# power_stage.net
KiCad netlist of a schematic drawn in Altium Designer
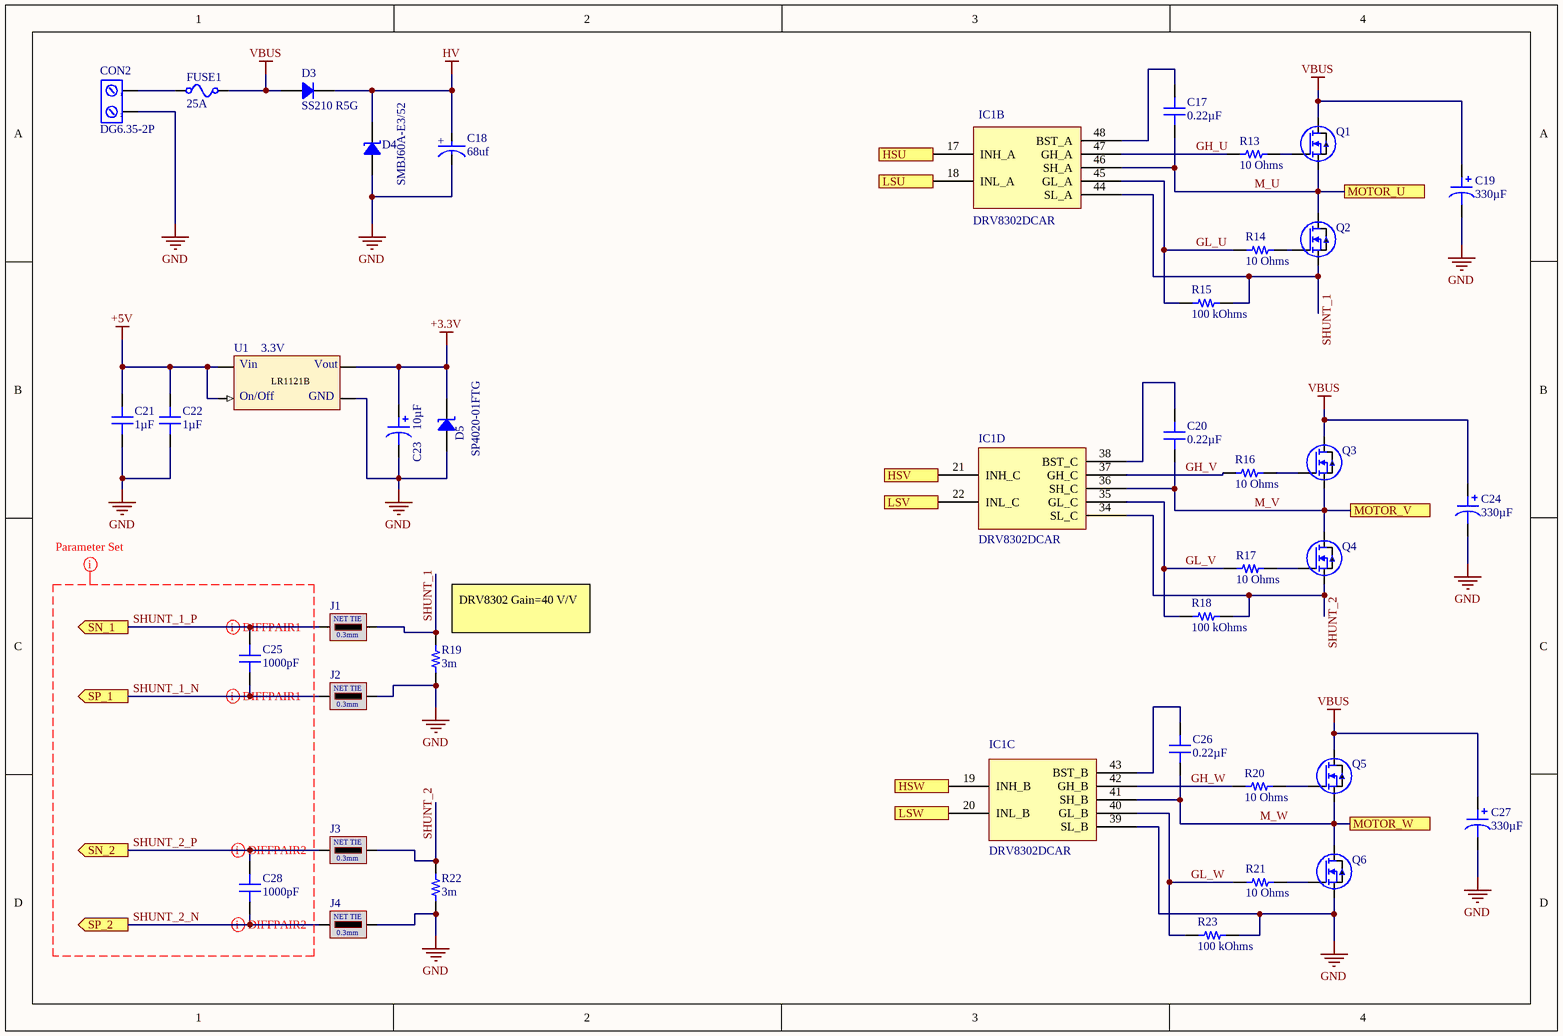
[diagram p0: power stage.SchDoc]

(export (version "E")
  (design (tool "Eeschema 10.0.6"))
  (components
    (comp (ref "C17")
      (value "0.22µF")
      (footprint "CAP 0603_1608")
      (description "CAP CER 0603 220NF 16V X7R 10%")
      (fields (field (name "PART NUMBER") "C0603C224K4RECAUTO") (field (name "MANUFACTURER") "KEMET"))
      (libsource (lib "Celestial Altium Library - altium_library") (part "Capacitor"))
    )
    (comp (ref "C18")
      (value "68uf")
      (footprint "10x10 radial smd cap")
      (description "68uf 100V 85C")
      (libsource (lib "My_Library_SMD_Electrlytic_Capacitor") (part "SC1J686M10010VR"))
    )
    (comp (ref "C19")
      (value "330µF")
      (footprint "CAP TH ALUM ELEC D10.00mm S5.00mm H26.50mm")
      (description "63V 331UF 20% HIGH RELIA-LEADED")
      (fields (field (name "PART NUMBER") "UHW1J331MPD") (field (name "MANUFACTURER") "Nichicon"))
      (libsource (lib "Celestial Altium Library - altium_library") (part "Polarised Capacitor"))
    )
    (comp (ref "C20")
      (value "0.22µF")
      (footprint "CAP 0603_1608")
      (description "CAP CER 0603 220NF 16V X7R 10%")
      (fields (field (name "PART NUMBER") "C0603C224K4RECAUTO") (field (name "MANUFACTURER") "KEMET"))
      (libsource (lib "Celestial Altium Library - altium_library") (part "Capacitor"))
    )
    (comp (ref "C21")
      (value "1µF")
      (footprint "CAP 0402_1005")
      (description "CAP CER 1UF 10V X7S 0402")
      (fields
        (field (name "PART NUMBER") "GRM155C71A105KE11D")
        (field (name "MANUFACTURER") "Murata Electronics")
      )
      (libsource (lib "Celestial Altium Library - altium_library") (part "Capacitor"))
    )
    (comp (ref "C22")
      (value "1µF")
      (footprint "CAP 0402_1005")
      (description "CAP CER 1UF 10V X7S 0402")
      (fields
        (field (name "PART NUMBER") "GRM155C71A105KE11D")
        (field (name "MANUFACTURER") "Murata Electronics")
      )
      (libsource (lib "Celestial Altium Library - altium_library") (part "Capacitor"))
    )
    (comp (ref "C23")
      (value "10µF")
      (footprint "CAP POL 1206_3216")
      (description "CAP TANT 10UF 10% 10V 1206")
      (fields (field (name "PART NUMBER") "T491S106K010AT") (field (name "MANUFACTURER") "KEMET"))
      (libsource (lib "Celestial Altium Library - altium_library") (part "Polarised Capacitor"))
    )
    (comp (ref "C24")
      (value "330µF")
      (footprint "CAP TH ALUM ELEC D10.00mm S5.00mm H26.50mm")
      (description "63V 331UF 20% HIGH RELIA-LEADED")
      (fields (field (name "PART NUMBER") "UHW1J331MPD") (field (name "MANUFACTURER") "Nichicon"))
      (libsource (lib "Celestial Altium Library - altium_library") (part "Polarised Capacitor"))
    )
    (comp (ref "C25")
      (value "1000pF")
      (footprint "CAP 0805_2012")
      (description "CAP CER 1000PF 100V X7R 0805")
      (fields (field (name "PART NUMBER") "CC0805JRX7R0BB102") (field (name "MANUFACTURER") "Yageo"))
      (libsource (lib "Celestial Altium Library - altium_library") (part "Capacitor"))
    )
    (comp (ref "C26")
      (value "0.22µF")
      (footprint "CAP 0603_1608")
      (description "CAP CER 0603 220NF 16V X7R 10%")
      (fields (field (name "PART NUMBER") "C0603C224K4RECAUTO") (field (name "MANUFACTURER") "KEMET"))
      (libsource (lib "Celestial Altium Library - altium_library") (part "Capacitor"))
    )
    (comp (ref "C27")
      (value "330µF")
      (footprint "CAP TH ALUM ELEC D10.00mm S5.00mm H26.50mm")
      (description "63V 331UF 20% HIGH RELIA-LEADED")
      (fields (field (name "PART NUMBER") "UHW1J331MPD") (field (name "MANUFACTURER") "Nichicon"))
      (libsource (lib "Celestial Altium Library - altium_library") (part "Polarised Capacitor"))
    )
    (comp (ref "C28")
      (value "1000pF")
      (footprint "CAP 0805_2012")
      (description "CAP CER 1000PF 100V X7R 0805")
      (fields (field (name "PART NUMBER") "CC0805JRX7R0BB102") (field (name "MANUFACTURER") "Yageo"))
      (libsource (lib "Celestial Altium Library - altium_library") (part "Capacitor"))
    )
    (comp (ref "CON2")
      (value "DG6.35-2P")
      (footprint "DG636-6.35-2P")
      (libsource (lib "My_Library_PCB_Terminal") (part "DG6.35-2P"))
    )
    (comp (ref "D3")
      (value "SS210 R5G")
      (footprint "DO214AA SMB")
      (description "DIODE SCHOTTKY 100V 2A DO214AA")
      (fields (field (name "MANUFACTURER") "Taiwan Semiconductor Corporation"))
      (libsource (lib "Celestial Altium Library - altium_library") (part "Diode"))
    )
    (comp (ref "D4")
      (value "SMBJ60A-E3/52")
      (footprint "DO214AA SMB")
      (description "TVS DIODE 60V 96.8V DO214AA")
      (fields (field (name "MANUFACTURER") "Vishay Semiconductor Diodes Division"))
      (libsource (lib "Celestial Altium Library - altium_library") (part "DIODE TVS UNI"))
    )
    (comp (ref "D5")
      (value "SP4020-01FTG")
      (footprint "SOD323")
      (description "TVS DIODE 3.3V 21.8V SOD323")
      (fields (field (name "MANUFACTURER") "Littelfuse Inc."))
      (libsource (lib "Celestial Altium Library - altium_library") (part "DIODE TVS UNI"))
    )
    (comp (ref "FUSE1")
      (value "25A")
      (footprint "3522 ATOF FUSE")
      (description "3522 ATOF automotive fuse")
      (libsource (lib "My_Library_ATOF_Fuse") (part "ATOF Fuse 3522"))
    )
    (comp (ref "IC1")
      (value "DRV8302DCAR")
      (footprint "TI HTSSOP-56 DCA")
      (description "IC MOTOR DRIVER 8V-60V 56HTSSOP")
      (fields (field (name "MANUFACTURER") "Texas Instruments"))
      (libsource (lib "Celestial Altium Library - altium_library") (part "TI DRV8302"))
    )
    (comp (ref "J1")
      (value "NET TIE 1")
      (footprint "net_tie_03mm")
      (libsource (lib "My_Library_Net_tie") (part "NET TIE 1"))
    )
    (comp (ref "J2")
      (value "NET TIE 1")
      (footprint "net_tie_03mm")
      (libsource (lib "My_Library_Net_tie") (part "NET TIE 1"))
    )
    (comp (ref "J3")
      (value "NET TIE 1")
      (footprint "net_tie_03mm")
      (libsource (lib "My_Library_Net_tie") (part "NET TIE 1"))
    )
    (comp (ref "J4")
      (value "NET TIE 1")
      (footprint "net_tie_03mm")
      (libsource (lib "My_Library_Net_tie") (part "NET TIE 1"))
    )
    (comp (ref "Q1")
      (value "STB100N10F7")
      (footprint "D2PAK")
      (libsource (lib "My_library_Mosfet") (part "STB100N10F7"))
    )
    (comp (ref "Q2")
      (value "STB100N10F7")
      (footprint "D2PAK")
      (libsource (lib "My_library_Mosfet") (part "STB100N10F7"))
    )
    (comp (ref "Q3")
      (value "STB100N10F7")
      (footprint "D2PAK")
      (libsource (lib "My_library_Mosfet") (part "STB100N10F7"))
    )
    (comp (ref "Q4")
      (value "STB100N10F7")
      (footprint "D2PAK")
      (libsource (lib "My_library_Mosfet") (part "STB100N10F7"))
    )
    (comp (ref "Q5")
      (value "STB100N10F7")
      (footprint "D2PAK")
      (libsource (lib "My_library_Mosfet") (part "STB100N10F7"))
    )
    (comp (ref "Q6")
      (value "STB100N10F7")
      (footprint "D2PAK")
      (libsource (lib "My_library_Mosfet") (part "STB100N10F7"))
    )
    (comp (ref "R13")
      (value "10 Ohms")
      (footprint "RES 1206_3216")
      (description "CRGCQ 1206 10R 1%")
      (fields
        (field (name "PART NUMBER") "CRGCQ1206F10R")
        (field (name "MANUFACTURER") "TE Connectivity Passive Product")
      )
      (libsource (lib "Celestial Altium Library - altium_library") (part "Resistor"))
    )
    (comp (ref "R14")
      (value "10 Ohms")
      (footprint "RES 1206_3216")
      (description "CRGCQ 1206 10R 1%")
      (fields
        (field (name "PART NUMBER") "CRGCQ1206F10R")
        (field (name "MANUFACTURER") "TE Connectivity Passive Product")
      )
      (libsource (lib "Celestial Altium Library - altium_library") (part "Resistor"))
    )
    (comp (ref "R15")
      (value "100 kOhms")
      (footprint "RES 1206_3216")
      (description "RES SMD 100K OHM 1% 1/4W 1206")
      (fields
        (field (name "PART NUMBER") "CRG1206F100K")
        (field (name "MANUFACTURER") "TE Connectivity Passive Product")
      )
      (libsource (lib "Celestial Altium Library - altium_library") (part "Resistor"))
    )
    (comp (ref "R16")
      (value "10 Ohms")
      (footprint "RES 1206_3216")
      (description "CRGCQ 1206 10R 1%")
      (fields
        (field (name "PART NUMBER") "CRGCQ1206F10R")
        (field (name "MANUFACTURER") "TE Connectivity Passive Product")
      )
      (libsource (lib "Celestial Altium Library - altium_library") (part "Resistor"))
    )
    (comp (ref "R17")
      (value "10 Ohms")
      (footprint "RES 1206_3216")
      (description "CRGCQ 1206 10R 1%")
      (fields
        (field (name "PART NUMBER") "CRGCQ1206F10R")
        (field (name "MANUFACTURER") "TE Connectivity Passive Product")
      )
      (libsource (lib "Celestial Altium Library - altium_library") (part "Resistor"))
    )
    (comp (ref "R18")
      (value "100 kOhms")
      (footprint "RES 1206_3216")
      (description "RES SMD 100K OHM 1% 1/4W 1206")
      (fields
        (field (name "PART NUMBER") "CRG1206F100K")
        (field (name "MANUFACTURER") "TE Connectivity Passive Product")
      )
      (libsource (lib "Celestial Altium Library - altium_library") (part "Resistor"))
    )
    (comp (ref "R19")
      (value "3m")
      (footprint "2512_bvt")
      (description "SMT Resistor")
      (libsource (lib "My_Library_Shunt_Resistor") (part "BVT2512"))
    )
    (comp (ref "R20")
      (value "10 Ohms")
      (footprint "RES 1206_3216")
      (description "CRGCQ 1206 10R 1%")
      (fields
        (field (name "PART NUMBER") "CRGCQ1206F10R")
        (field (name "MANUFACTURER") "TE Connectivity Passive Product")
      )
      (libsource (lib "Celestial Altium Library - altium_library") (part "Resistor"))
    )
    (comp (ref "R21")
      (value "10 Ohms")
      (footprint "RES 1206_3216")
      (description "CRGCQ 1206 10R 1%")
      (fields
        (field (name "PART NUMBER") "CRGCQ1206F10R")
        (field (name "MANUFACTURER") "TE Connectivity Passive Product")
      )
      (libsource (lib "Celestial Altium Library - altium_library") (part "Resistor"))
    )
    (comp (ref "R22")
      (value "3m")
      (footprint "2512_bvt")
      (description "SMT Resistor")
      (libsource (lib "My_Library_Shunt_Resistor") (part "BVT2512"))
    )
    (comp (ref "R23")
      (value "100 kOhms")
      (footprint "RES 1206_3216")
      (description "RES SMD 100K OHM 1% 1/4W 1206")
      (fields
        (field (name "PART NUMBER") "CRG1206F100K")
        (field (name "MANUFACTURER") "TE Connectivity Passive Product")
      )
      (libsource (lib "Celestial Altium Library - altium_library") (part "Resistor"))
    )
    (comp (ref "U1")
      (value "3.3V")
      (footprint "SOT25_LR2111")
      (description "200mA 7V LDO")
      (libsource (lib "My_Library_Linear_Regulator") (part "LR1121B_3V3"))
    )
  )
  (nets
    (net (code "1") (name "+3.3V") (class "Default")
      (node (ref "C23") (pin "1") (pinfunction "1_1") (pintype "passive"))
      (node (ref "D5") (pin "2") (pinfunction "2_2") (pintype "passive"))
      (node (ref "U1") (pin "1") (pinfunction "Vout_1") (pintype "power_in"))
    )
    (net (code "2") (name "+5V") (class "Default")
      (node (ref "C21") (pin "2") (pinfunction "2_2") (pintype "passive"))
      (node (ref "C22") (pin "2") (pinfunction "2_2") (pintype "passive"))
      (node (ref "U1") (pin "3") (pinfunction "Vin_3") (pintype "power_in"))
      (node (ref "U1") (pin "4") (pinfunction "ON/OFF_4") (pintype "input"))
    )
    (net (code "3") (name "/GH_U") (class "Default")
      (node (ref "IC1") (pin "47") (pinfunction "GH_A_47") (pintype "passive"))
      (node (ref "R13") (pin "1") (pinfunction "1_1") (pintype "passive"))
    )
    (net (code "4") (name "/GH_V") (class "Default")
      (node (ref "IC1") (pin "37") (pinfunction "GH_C_37") (pintype "passive"))
      (node (ref "R16") (pin "1") (pinfunction "1_1") (pintype "passive"))
    )
    (net (code "5") (name "/GH_W") (class "Default")
      (node (ref "IC1") (pin "42") (pinfunction "GH_B_42") (pintype "passive"))
      (node (ref "R20") (pin "1") (pinfunction "1_1") (pintype "passive"))
    )
    (net (code "6") (name "/GL_U") (class "Default")
      (node (ref "IC1") (pin "45") (pinfunction "GL_A_45") (pintype "passive"))
      (node (ref "R14") (pin "1") (pinfunction "1_1") (pintype "passive"))
      (node (ref "R15") (pin "1") (pinfunction "1_1") (pintype "passive"))
    )
    (net (code "7") (name "/GL_V") (class "Default")
      (node (ref "IC1") (pin "35") (pinfunction "GL_C_35") (pintype "passive"))
      (node (ref "R17") (pin "1") (pinfunction "1_1") (pintype "passive"))
      (node (ref "R18") (pin "1") (pinfunction "1_1") (pintype "passive"))
    )
    (net (code "8") (name "/GL_W") (class "Default")
      (node (ref "IC1") (pin "40") (pinfunction "GL_B_40") (pintype "passive"))
      (node (ref "R21") (pin "1") (pinfunction "1_1") (pintype "passive"))
      (node (ref "R23") (pin "1") (pinfunction "1_1") (pintype "passive"))
    )
    (net (code "9") (name "/HSU") (class "Default")
      (node (ref "IC1") (pin "17") (pinfunction "INH_A_17") (pintype "passive"))
    )
    (net (code "10") (name "/HSV") (class "Default")
      (node (ref "IC1") (pin "21") (pinfunction "INH_C_21") (pintype "passive"))
    )
    (net (code "11") (name "/HSW") (class "Default")
      (node (ref "IC1") (pin "19") (pinfunction "INH_B_19") (pintype "passive"))
    )
    (net (code "12") (name "/LSU") (class "Default")
      (node (ref "IC1") (pin "18") (pinfunction "INL_A_18") (pintype "passive"))
    )
    (net (code "13") (name "/LSV") (class "Default")
      (node (ref "IC1") (pin "22") (pinfunction "INL_C_22") (pintype "passive"))
    )
    (net (code "14") (name "/LSW") (class "Default")
      (node (ref "IC1") (pin "20") (pinfunction "INL_B_20") (pintype "passive"))
    )
    (net (code "15") (name "/M_U") (class "Default")
      (node (ref "C17") (pin "1") (pinfunction "1_1") (pintype "passive"))
      (node (ref "IC1") (pin "46") (pinfunction "SH_A_46") (pintype "passive"))
      (node (ref "Q1") (pin "3") (pinfunction "S_3") (pintype "passive"))
      (node (ref "Q2") (pin "2") (pinfunction "D_2") (pintype "passive"))
    )
    (net (code "16") (name "/M_V") (class "Default")
      (node (ref "C20") (pin "1") (pinfunction "1_1") (pintype "passive"))
      (node (ref "IC1") (pin "36") (pinfunction "SH_C_36") (pintype "passive"))
      (node (ref "Q3") (pin "3") (pinfunction "S_3") (pintype "passive"))
      (node (ref "Q4") (pin "2") (pinfunction "D_2") (pintype "passive"))
    )
    (net (code "17") (name "/M_W") (class "Default")
      (node (ref "C26") (pin "1") (pinfunction "1_1") (pintype "passive"))
      (node (ref "IC1") (pin "41") (pinfunction "SH_B_41") (pintype "passive"))
      (node (ref "Q5") (pin "3") (pinfunction "S_3") (pintype "passive"))
      (node (ref "Q6") (pin "2") (pinfunction "D_2") (pintype "passive"))
    )
    (net (code "18") (name "/SHUNT_1") (class "Default")
      (node (ref "IC1") (pin "44") (pinfunction "SL_A_44") (pintype "passive"))
      (node (ref "J1") (pin "2") (pinfunction "2_2") (pintype "passive"))
      (node (ref "Q2") (pin "3") (pinfunction "S_3") (pintype "passive"))
      (node (ref "R15") (pin "2") (pinfunction "2_2") (pintype "passive"))
      (node (ref "R19") (pin "2") (pinfunction "2_2") (pintype "passive"))
    )
    (net (code "19") (name "/SHUNT_1_N") (class "Default")
      (node (ref "C25") (pin "1") (pinfunction "1_1") (pintype "passive"))
      (node (ref "J2") (pin "1") (pinfunction "1_1") (pintype "passive"))
    )
    (net (code "20") (name "/SHUNT_1_P") (class "Default")
      (node (ref "C25") (pin "2") (pinfunction "2_2") (pintype "passive"))
      (node (ref "J1") (pin "1") (pinfunction "1_1") (pintype "passive"))
    )
    (net (code "21") (name "/SHUNT_2") (class "Default")
      (node (ref "IC1") (pin "34") (pinfunction "SL_C_34") (pintype "passive"))
      (node (ref "J3") (pin "2") (pinfunction "2_2") (pintype "passive"))
      (node (ref "Q4") (pin "3") (pinfunction "S_3") (pintype "passive"))
      (node (ref "R18") (pin "2") (pinfunction "2_2") (pintype "passive"))
      (node (ref "R22") (pin "2") (pinfunction "2_2") (pintype "passive"))
    )
    (net (code "22") (name "/SHUNT_2_N") (class "Default")
      (node (ref "C28") (pin "1") (pinfunction "1_1") (pintype "passive"))
      (node (ref "J4") (pin "1") (pinfunction "1_1") (pintype "passive"))
    )
    (net (code "23") (name "/SHUNT_2_P") (class "Default")
      (node (ref "C28") (pin "2") (pinfunction "2_2") (pintype "passive"))
      (node (ref "J3") (pin "1") (pinfunction "1_1") (pintype "passive"))
    )
    (net (code "24") (name "GND") (class "Default")
      (node (ref "C18") (pin "1") (pinfunction "C_1") (pintype "passive"))
      (node (ref "C19") (pin "2") (pinfunction "2_2") (pintype "passive"))
      (node (ref "C21") (pin "1") (pinfunction "1_1") (pintype "passive"))
      (node (ref "C22") (pin "1") (pinfunction "1_1") (pintype "passive"))
      (node (ref "C23") (pin "2") (pinfunction "2_2") (pintype "passive"))
      (node (ref "C24") (pin "2") (pinfunction "2_2") (pintype "passive"))
      (node (ref "C27") (pin "2") (pinfunction "2_2") (pintype "passive"))
      (node (ref "CON2") (pin "2") (pinfunction "2_2") (pintype "passive"))
      (node (ref "D4") (pin "1") (pinfunction "1_1") (pintype "passive"))
      (node (ref "D5") (pin "1") (pinfunction "1_1") (pintype "passive"))
      (node (ref "IC1") (pin "39") (pinfunction "SL_B_39") (pintype "passive"))
      (node (ref "J2") (pin "2") (pinfunction "2_2") (pintype "passive"))
      (node (ref "J4") (pin "2") (pinfunction "2_2") (pintype "passive"))
      (node (ref "Q6") (pin "3") (pinfunction "S_3") (pintype "passive"))
      (node (ref "R19") (pin "1") (pinfunction "1_1") (pintype "passive"))
      (node (ref "R22") (pin "1") (pinfunction "1_1") (pintype "passive"))
      (node (ref "R23") (pin "2") (pinfunction "2_2") (pintype "passive"))
      (node (ref "U1") (pin "2") (pinfunction "Vss_2") (pintype "passive"))
    )
    (net (code "25") (name "HV") (class "Default")
      (node (ref "C18") (pin "2") (pinfunction "A_2") (pintype "passive"))
      (node (ref "D3") (pin "2") (pinfunction "2_2") (pintype "passive"))
      (node (ref "D4") (pin "2") (pinfunction "2_2") (pintype "passive"))
    )
    (net (code "26") (name "Net-(CON2-Pad1)") (class "Default")
      (node (ref "CON2") (pin "1") (pinfunction "1_1") (pintype "passive"))
      (node (ref "FUSE1") (pin "1") (pinfunction "1_1") (pintype "passive"))
    )
    (net (code "27") (name "Net-(IC1B-BST_A)") (class "Default")
      (node (ref "C17") (pin "2") (pinfunction "2_2") (pintype "passive"))
      (node (ref "IC1") (pin "48") (pinfunction "BST_A_48") (pintype "passive"))
    )
    (net (code "28") (name "Net-(IC1C-BST_B)") (class "Default")
      (node (ref "C26") (pin "2") (pinfunction "2_2") (pintype "passive"))
      (node (ref "IC1") (pin "43") (pinfunction "BST_B_43") (pintype "passive"))
    )
    (net (code "29") (name "Net-(IC1D-BST_C)") (class "Default")
      (node (ref "C20") (pin "2") (pinfunction "2_2") (pintype "passive"))
      (node (ref "IC1") (pin "38") (pinfunction "BST_C_38") (pintype "passive"))
    )
    (net (code "30") (name "Net-(Q1-G)") (class "Default")
      (node (ref "Q1") (pin "1") (pinfunction "G_1") (pintype "passive"))
      (node (ref "R13") (pin "2") (pinfunction "2_2") (pintype "passive"))
    )
    (net (code "31") (name "Net-(Q2-G)") (class "Default")
      (node (ref "Q2") (pin "1") (pinfunction "G_1") (pintype "passive"))
      (node (ref "R14") (pin "2") (pinfunction "2_2") (pintype "passive"))
    )
    (net (code "32") (name "Net-(Q3-G)") (class "Default")
      (node (ref "Q3") (pin "1") (pinfunction "G_1") (pintype "passive"))
      (node (ref "R16") (pin "2") (pinfunction "2_2") (pintype "passive"))
    )
    (net (code "33") (name "Net-(Q4-G)") (class "Default")
      (node (ref "Q4") (pin "1") (pinfunction "G_1") (pintype "passive"))
      (node (ref "R17") (pin "2") (pinfunction "2_2") (pintype "passive"))
    )
    (net (code "34") (name "Net-(Q5-G)") (class "Default")
      (node (ref "Q5") (pin "1") (pinfunction "G_1") (pintype "passive"))
      (node (ref "R20") (pin "2") (pinfunction "2_2") (pintype "passive"))
    )
    (net (code "35") (name "Net-(Q6-G)") (class "Default")
      (node (ref "Q6") (pin "1") (pinfunction "G_1") (pintype "passive"))
      (node (ref "R21") (pin "2") (pinfunction "2_2") (pintype "passive"))
    )
    (net (code "36") (name "VBUS") (class "Default")
      (node (ref "C19") (pin "1") (pinfunction "1_1") (pintype "passive"))
      (node (ref "C24") (pin "1") (pinfunction "1_1") (pintype "passive"))
      (node (ref "C27") (pin "1") (pinfunction "1_1") (pintype "passive"))
      (node (ref "D3") (pin "1") (pinfunction "1_1") (pintype "passive"))
      (node (ref "FUSE1") (pin "2") (pinfunction "2_2") (pintype "passive"))
      (node (ref "Q1") (pin "2") (pinfunction "D_2") (pintype "passive"))
      (node (ref "Q3") (pin "2") (pinfunction "D_2") (pintype "passive"))
      (node (ref "Q5") (pin "2") (pinfunction "D_2") (pintype "passive"))
    )
  )
)
